# Sheet1.net
KiCad netlist of a schematic drawn in Altium Designer
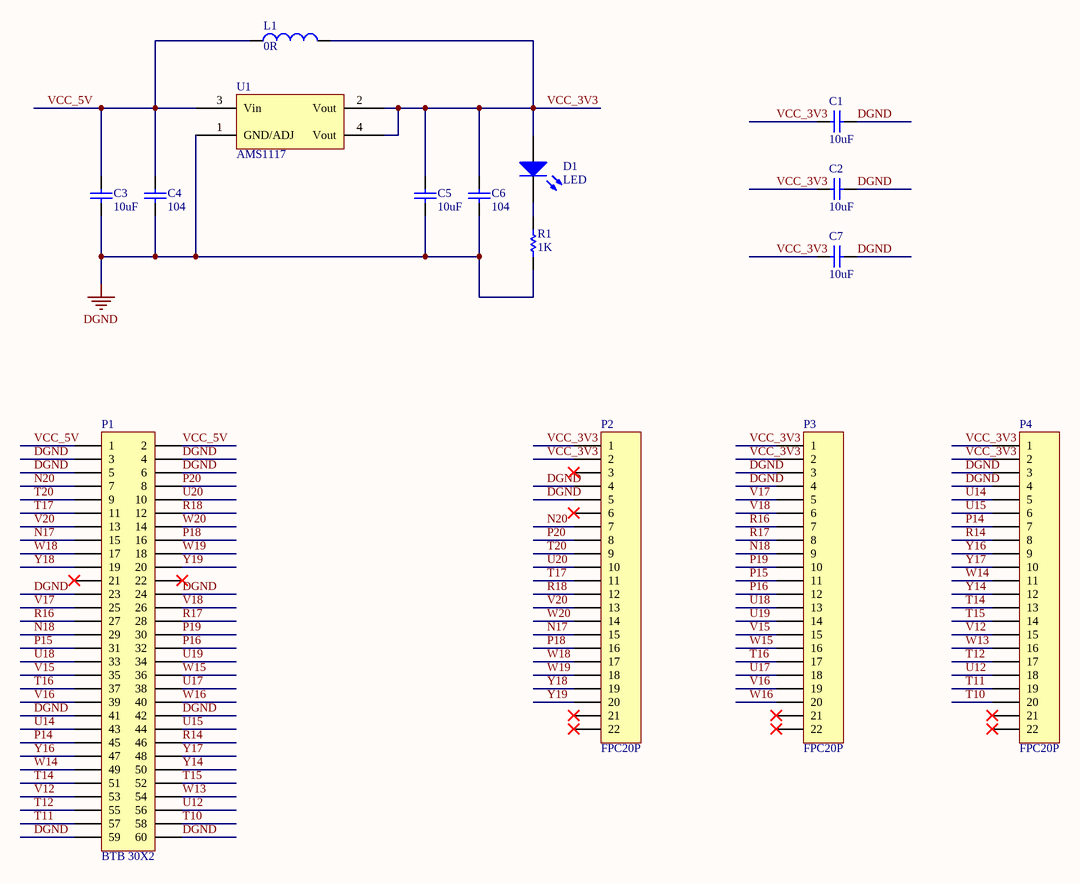
[diagram p0: Sheet1.SchDoc]

(export (version "E")
  (design (tool "Eeschema 10.0.6"))
  (components
    (comp (ref "C1")
      (value "10uF")
      (footprint "R0805")
      (description "Capacitor")
      (fields (field (name "Comment") "Cap") (field (name "PUBLISHER") "Altium Limited"))
      (libsource (lib "Miscellaneous Devices") (part "Cap"))
    )
    (comp (ref "C2")
      (value "10uF")
      (footprint "R0805")
      (description "Capacitor")
      (fields (field (name "Comment") "Cap") (field (name "PUBLISHER") "Altium Limited"))
      (libsource (lib "Miscellaneous Devices") (part "Cap"))
    )
    (comp (ref "C3")
      (value "10uF")
      (footprint "R0805")
      (description "Capacitor")
      (fields (field (name "Comment") "Cap") (field (name "PUBLISHER") "Altium Limited"))
      (libsource (lib "Miscellaneous Devices") (part "Cap"))
    )
    (comp (ref "C4")
      (value "104")
      (footprint "R0805")
      (description "Capacitor")
      (fields (field (name "Comment") "Cap") (field (name "PUBLISHER") "Altium Limited"))
      (libsource (lib "Miscellaneous Devices") (part "Cap"))
    )
    (comp (ref "C5")
      (value "10uF")
      (footprint "R0805")
      (description "Capacitor")
      (fields (field (name "Comment") "Cap") (field (name "PUBLISHER") "Altium Limited"))
      (libsource (lib "Miscellaneous Devices") (part "Cap"))
    )
    (comp (ref "C6")
      (value "104")
      (footprint "R0805")
      (description "Capacitor")
      (fields (field (name "Comment") "Cap") (field (name "PUBLISHER") "Altium Limited"))
      (libsource (lib "Miscellaneous Devices") (part "Cap"))
    )
    (comp (ref "C7")
      (value "10uF")
      (footprint "R0805")
      (description "Capacitor")
      (fields (field (name "Comment") "Cap") (field (name "PUBLISHER") "Altium Limited"))
      (libsource (lib "Miscellaneous Devices") (part "Cap"))
    )
    (comp (ref "D1")
      (value "LED")
      (footprint "LED0805红")
      (description "Typical INFRARED GaAs LED")
      (fields (field (name "PUBLISHER") "Altium Limited"))
      (libsource (lib "Miscellaneous Devices") (part "LED0"))
    )
    (comp (ref "L1")
      (value "0R")
      (footprint "R0805")
      (description "Inductor")
      (fields (field (name "PUBLISHER") "Altium Limited"))
      (libsource (lib "Miscellaneous Devices") (part "Inductor"))
    )
    (comp (ref "P1")
      (value "BTB 30X2")
      (footprint "BTBCON_0.8mm_60P")
      (description "Header, 30-Pin, Dual row")
      (fields (field (name "PUBLISHER") "Altium Limited"))
      (libsource (lib "Miscellaneous Connectors") (part "Header 30X2"))
    )
    (comp (ref "P2")
      (value "FPC20P")
      (footprint "FPC20Pin")
      (description "Header, 22-Pin")
      (fields (field (name "PUBLISHER") "Altium Limited"))
      (libsource (lib "Miscellaneous Connectors") (part "Header 22"))
    )
    (comp (ref "P3")
      (value "FPC20P")
      (footprint "FPC20Pin")
      (description "Header, 22-Pin")
      (fields (field (name "PUBLISHER") "Altium Limited"))
      (libsource (lib "Miscellaneous Connectors") (part "Header 22"))
    )
    (comp (ref "P4")
      (value "FPC20P")
      (footprint "FPC20Pin")
      (description "Header, 22-Pin")
      (fields (field (name "PUBLISHER") "Altium Limited"))
      (libsource (lib "Miscellaneous Connectors") (part "Header 22"))
    )
    (comp (ref "R1")
      (value "1K")
      (footprint "R0805")
      (description "Resistor")
      (fields (field (name "Comment") "Res1") (field (name "PUBLISHER") "Altium Limited"))
      (libsource (lib "Miscellaneous Devices") (part "Res1"))
    )
    (comp (ref "U1")
      (value "AMS1117")
      (footprint "SOT-223   AMS1117")
      (libsource (lib "MySchlib") (part "AMS1117"))
    )
  )
  (nets
    (net (code "1") (name "/N17") (class "Default")
      (node (ref "P1") (pin "15") (pinfunction "15_15") (pintype "passive"))
      (node (ref "P2") (pin "15") (pinfunction "15_15") (pintype "passive"))
    )
    (net (code "2") (name "/N18") (class "Default")
      (node (ref "P1") (pin "29") (pinfunction "29_29") (pintype "passive"))
      (node (ref "P3") (pin "9") (pinfunction "9_9") (pintype "passive"))
    )
    (net (code "3") (name "/N20") (class "Default")
      (node (ref "P1") (pin "7") (pinfunction "7_7") (pintype "passive"))
      (node (ref "P2") (pin "7") (pinfunction "7_7") (pintype "passive"))
    )
    (net (code "4") (name "/P14") (class "Default")
      (node (ref "P1") (pin "45") (pinfunction "45_45") (pintype "passive"))
      (node (ref "P4") (pin "7") (pinfunction "7_7") (pintype "passive"))
    )
    (net (code "5") (name "/P15") (class "Default")
      (node (ref "P1") (pin "31") (pinfunction "31_31") (pintype "passive"))
      (node (ref "P3") (pin "11") (pinfunction "11_11") (pintype "passive"))
    )
    (net (code "6") (name "/P16") (class "Default")
      (node (ref "P1") (pin "32") (pinfunction "32_32") (pintype "passive"))
      (node (ref "P3") (pin "12") (pinfunction "12_12") (pintype "passive"))
    )
    (net (code "7") (name "/P18") (class "Default")
      (node (ref "P1") (pin "16") (pinfunction "16_16") (pintype "passive"))
      (node (ref "P2") (pin "16") (pinfunction "16_16") (pintype "passive"))
    )
    (net (code "8") (name "/P19") (class "Default")
      (node (ref "P1") (pin "30") (pinfunction "30_30") (pintype "passive"))
      (node (ref "P3") (pin "10") (pinfunction "10_10") (pintype "passive"))
    )
    (net (code "9") (name "/P20") (class "Default")
      (node (ref "P1") (pin "8") (pinfunction "8_8") (pintype "passive"))
      (node (ref "P2") (pin "8") (pinfunction "8_8") (pintype "passive"))
    )
    (net (code "10") (name "/R14") (class "Default")
      (node (ref "P1") (pin "46") (pinfunction "46_46") (pintype "passive"))
      (node (ref "P4") (pin "8") (pinfunction "8_8") (pintype "passive"))
    )
    (net (code "11") (name "/R16") (class "Default")
      (node (ref "P1") (pin "27") (pinfunction "27_27") (pintype "passive"))
      (node (ref "P3") (pin "7") (pinfunction "7_7") (pintype "passive"))
    )
    (net (code "12") (name "/R17") (class "Default")
      (node (ref "P1") (pin "28") (pinfunction "28_28") (pintype "passive"))
      (node (ref "P3") (pin "8") (pinfunction "8_8") (pintype "passive"))
    )
    (net (code "13") (name "/R18") (class "Default")
      (node (ref "P1") (pin "12") (pinfunction "12_12") (pintype "passive"))
      (node (ref "P2") (pin "12") (pinfunction "12_12") (pintype "passive"))
    )
    (net (code "14") (name "/T10") (class "Default")
      (node (ref "P1") (pin "58") (pinfunction "58_58") (pintype "passive"))
      (node (ref "P4") (pin "20") (pinfunction "20_20") (pintype "passive"))
    )
    (net (code "15") (name "/T11") (class "Default")
      (node (ref "P1") (pin "57") (pinfunction "57_57") (pintype "passive"))
      (node (ref "P4") (pin "19") (pinfunction "19_19") (pintype "passive"))
    )
    (net (code "16") (name "/T12") (class "Default")
      (node (ref "P1") (pin "55") (pinfunction "55_55") (pintype "passive"))
      (node (ref "P4") (pin "17") (pinfunction "17_17") (pintype "passive"))
    )
    (net (code "17") (name "/T14") (class "Default")
      (node (ref "P1") (pin "51") (pinfunction "51_51") (pintype "passive"))
      (node (ref "P4") (pin "13") (pinfunction "13_13") (pintype "passive"))
    )
    (net (code "18") (name "/T15") (class "Default")
      (node (ref "P1") (pin "52") (pinfunction "52_52") (pintype "passive"))
      (node (ref "P4") (pin "14") (pinfunction "14_14") (pintype "passive"))
    )
    (net (code "19") (name "/T16") (class "Default")
      (node (ref "P1") (pin "37") (pinfunction "37_37") (pintype "passive"))
      (node (ref "P3") (pin "17") (pinfunction "17_17") (pintype "passive"))
    )
    (net (code "20") (name "/T17") (class "Default")
      (node (ref "P1") (pin "11") (pinfunction "11_11") (pintype "passive"))
      (node (ref "P2") (pin "11") (pinfunction "11_11") (pintype "passive"))
    )
    (net (code "21") (name "/T20") (class "Default")
      (node (ref "P1") (pin "9") (pinfunction "9_9") (pintype "passive"))
      (node (ref "P2") (pin "9") (pinfunction "9_9") (pintype "passive"))
    )
    (net (code "22") (name "/U12") (class "Default")
      (node (ref "P1") (pin "56") (pinfunction "56_56") (pintype "passive"))
      (node (ref "P4") (pin "18") (pinfunction "18_18") (pintype "passive"))
    )
    (net (code "23") (name "/U14") (class "Default")
      (node (ref "P1") (pin "43") (pinfunction "43_43") (pintype "passive"))
      (node (ref "P4") (pin "5") (pinfunction "5_5") (pintype "passive"))
    )
    (net (code "24") (name "/U15") (class "Default")
      (node (ref "P1") (pin "44") (pinfunction "44_44") (pintype "passive"))
      (node (ref "P4") (pin "6") (pinfunction "6_6") (pintype "passive"))
    )
    (net (code "25") (name "/U17") (class "Default")
      (node (ref "P1") (pin "38") (pinfunction "38_38") (pintype "passive"))
      (node (ref "P3") (pin "18") (pinfunction "18_18") (pintype "passive"))
    )
    (net (code "26") (name "/U18") (class "Default")
      (node (ref "P1") (pin "33") (pinfunction "33_33") (pintype "passive"))
      (node (ref "P3") (pin "13") (pinfunction "13_13") (pintype "passive"))
    )
    (net (code "27") (name "/U19") (class "Default")
      (node (ref "P1") (pin "34") (pinfunction "34_34") (pintype "passive"))
      (node (ref "P3") (pin "14") (pinfunction "14_14") (pintype "passive"))
    )
    (net (code "28") (name "/U20") (class "Default")
      (node (ref "P1") (pin "10") (pinfunction "10_10") (pintype "passive"))
      (node (ref "P2") (pin "10") (pinfunction "10_10") (pintype "passive"))
    )
    (net (code "29") (name "/V12") (class "Default")
      (node (ref "P1") (pin "53") (pinfunction "53_53") (pintype "passive"))
      (node (ref "P4") (pin "15") (pinfunction "15_15") (pintype "passive"))
    )
    (net (code "30") (name "/V15") (class "Default")
      (node (ref "P1") (pin "35") (pinfunction "35_35") (pintype "passive"))
      (node (ref "P3") (pin "15") (pinfunction "15_15") (pintype "passive"))
    )
    (net (code "31") (name "/V16") (class "Default")
      (node (ref "P1") (pin "39") (pinfunction "39_39") (pintype "passive"))
      (node (ref "P3") (pin "19") (pinfunction "19_19") (pintype "passive"))
    )
    (net (code "32") (name "/V17") (class "Default")
      (node (ref "P1") (pin "25") (pinfunction "25_25") (pintype "passive"))
      (node (ref "P3") (pin "5") (pinfunction "5_5") (pintype "passive"))
    )
    (net (code "33") (name "/V18") (class "Default")
      (node (ref "P1") (pin "26") (pinfunction "26_26") (pintype "passive"))
      (node (ref "P3") (pin "6") (pinfunction "6_6") (pintype "passive"))
    )
    (net (code "34") (name "/V20") (class "Default")
      (node (ref "P1") (pin "13") (pinfunction "13_13") (pintype "passive"))
      (node (ref "P2") (pin "13") (pinfunction "13_13") (pintype "passive"))
    )
    (net (code "35") (name "/VCC_3V3") (class "Default")
      (node (ref "C1") (pin "2") (pinfunction "2_2") (pintype "passive"))
      (node (ref "C2") (pin "2") (pinfunction "2_2") (pintype "passive"))
      (node (ref "C5") (pin "2") (pinfunction "2_2") (pintype "passive"))
      (node (ref "C6") (pin "2") (pinfunction "2_2") (pintype "passive"))
      (node (ref "C7") (pin "2") (pinfunction "2_2") (pintype "passive"))
      (node (ref "D1") (pin "1") (pinfunction "A_1") (pintype "passive"))
      (node (ref "L1") (pin "2") (pinfunction "2_2") (pintype "passive"))
      (node (ref "P2") (pin "1") (pinfunction "1_1") (pintype "passive"))
      (node (ref "P2") (pin "2") (pinfunction "2_2") (pintype "passive"))
      (node (ref "P3") (pin "1") (pinfunction "1_1") (pintype "passive"))
      (node (ref "P3") (pin "2") (pinfunction "2_2") (pintype "passive"))
      (node (ref "P4") (pin "1") (pinfunction "1_1") (pintype "passive"))
      (node (ref "P4") (pin "2") (pinfunction "2_2") (pintype "passive"))
      (node (ref "U1") (pin "2") (pinfunction "Vout_2") (pintype "passive"))
      (node (ref "U1") (pin "4") (pinfunction "Vout_4") (pintype "passive"))
    )
    (net (code "36") (name "/VCC_5V") (class "Default")
      (node (ref "C3") (pin "2") (pinfunction "2_2") (pintype "passive"))
      (node (ref "C4") (pin "2") (pinfunction "2_2") (pintype "passive"))
      (node (ref "L1") (pin "1") (pinfunction "1_1") (pintype "passive"))
      (node (ref "P1") (pin "1") (pinfunction "1_1") (pintype "passive"))
      (node (ref "P1") (pin "2") (pinfunction "2_2") (pintype "passive"))
      (node (ref "U1") (pin "3") (pinfunction "Vin_3") (pintype "passive"))
    )
    (net (code "37") (name "/W13") (class "Default")
      (node (ref "P1") (pin "54") (pinfunction "54_54") (pintype "passive"))
      (node (ref "P4") (pin "16") (pinfunction "16_16") (pintype "passive"))
    )
    (net (code "38") (name "/W14") (class "Default")
      (node (ref "P1") (pin "49") (pinfunction "49_49") (pintype "passive"))
      (node (ref "P4") (pin "11") (pinfunction "11_11") (pintype "passive"))
    )
    (net (code "39") (name "/W15") (class "Default")
      (node (ref "P1") (pin "36") (pinfunction "36_36") (pintype "passive"))
      (node (ref "P3") (pin "16") (pinfunction "16_16") (pintype "passive"))
    )
    (net (code "40") (name "/W16") (class "Default")
      (node (ref "P1") (pin "40") (pinfunction "40_40") (pintype "passive"))
      (node (ref "P3") (pin "20") (pinfunction "20_20") (pintype "passive"))
    )
    (net (code "41") (name "/W18") (class "Default")
      (node (ref "P1") (pin "17") (pinfunction "17_17") (pintype "passive"))
      (node (ref "P2") (pin "17") (pinfunction "17_17") (pintype "passive"))
    )
    (net (code "42") (name "/W19") (class "Default")
      (node (ref "P1") (pin "18") (pinfunction "18_18") (pintype "passive"))
      (node (ref "P2") (pin "18") (pinfunction "18_18") (pintype "passive"))
    )
    (net (code "43") (name "/W20") (class "Default")
      (node (ref "P1") (pin "14") (pinfunction "14_14") (pintype "passive"))
      (node (ref "P2") (pin "14") (pinfunction "14_14") (pintype "passive"))
    )
    (net (code "44") (name "/Y14") (class "Default")
      (node (ref "P1") (pin "50") (pinfunction "50_50") (pintype "passive"))
      (node (ref "P4") (pin "12") (pinfunction "12_12") (pintype "passive"))
    )
    (net (code "45") (name "/Y16") (class "Default")
      (node (ref "P1") (pin "47") (pinfunction "47_47") (pintype "passive"))
      (node (ref "P4") (pin "9") (pinfunction "9_9") (pintype "passive"))
    )
    (net (code "46") (name "/Y17") (class "Default")
      (node (ref "P1") (pin "48") (pinfunction "48_48") (pintype "passive"))
      (node (ref "P4") (pin "10") (pinfunction "10_10") (pintype "passive"))
    )
    (net (code "47") (name "/Y18") (class "Default")
      (node (ref "P1") (pin "19") (pinfunction "19_19") (pintype "passive"))
      (node (ref "P2") (pin "19") (pinfunction "19_19") (pintype "passive"))
    )
    (net (code "48") (name "/Y19") (class "Default")
      (node (ref "P1") (pin "20") (pinfunction "20_20") (pintype "passive"))
      (node (ref "P2") (pin "20") (pinfunction "20_20") (pintype "passive"))
    )
    (net (code "49") (name "DGND") (class "Default")
      (node (ref "C1") (pin "1") (pinfunction "1_1") (pintype "passive"))
      (node (ref "C2") (pin "1") (pinfunction "1_1") (pintype "passive"))
      (node (ref "C3") (pin "1") (pinfunction "1_1") (pintype "passive"))
      (node (ref "C4") (pin "1") (pinfunction "1_1") (pintype "passive"))
      (node (ref "C5") (pin "1") (pinfunction "1_1") (pintype "passive"))
      (node (ref "C6") (pin "1") (pinfunction "1_1") (pintype "passive"))
      (node (ref "C7") (pin "1") (pinfunction "1_1") (pintype "passive"))
      (node (ref "P1") (pin "23") (pinfunction "23_23") (pintype "passive"))
      (node (ref "P1") (pin "24") (pinfunction "24_24") (pintype "passive"))
      (node (ref "P1") (pin "3") (pinfunction "3_3") (pintype "passive"))
      (node (ref "P1") (pin "4") (pinfunction "4_4") (pintype "passive"))
      (node (ref "P1") (pin "41") (pinfunction "41_41") (pintype "passive"))
      (node (ref "P1") (pin "42") (pinfunction "42_42") (pintype "passive"))
      (node (ref "P1") (pin "5") (pinfunction "5_5") (pintype "passive"))
      (node (ref "P1") (pin "59") (pinfunction "59_59") (pintype "passive"))
      (node (ref "P1") (pin "6") (pinfunction "6_6") (pintype "passive"))
      (node (ref "P1") (pin "60") (pinfunction "60_60") (pintype "passive"))
      (node (ref "P2") (pin "4") (pinfunction "4_4") (pintype "passive"))
      (node (ref "P2") (pin "5") (pinfunction "5_5") (pintype "passive"))
      (node (ref "P3") (pin "3") (pinfunction "3_3") (pintype "passive"))
      (node (ref "P3") (pin "4") (pinfunction "4_4") (pintype "passive"))
      (node (ref "P4") (pin "3") (pinfunction "3_3") (pintype "passive"))
      (node (ref "P4") (pin "4") (pinfunction "4_4") (pintype "passive"))
      (node (ref "R1") (pin "1") (pinfunction "1_1") (pintype "passive"))
      (node (ref "U1") (pin "1") (pinfunction "GND/ADJ_1") (pintype "passive"))
    )
    (net (code "50") (name "Net-(D1-K)") (class "Default")
      (node (ref "D1") (pin "2") (pinfunction "K_2") (pintype "passive"))
      (node (ref "R1") (pin "2") (pinfunction "2_2") (pintype "passive"))
    )
    (net (code "51") (name "unconnected-(P1-Pad21)") (class "Default")
      (node (ref "P1") (pin "21") (pinfunction "21_21") (pintype "passive+no_connect"))
    )
    (net (code "52") (name "unconnected-(P1-Pad22)") (class "Default")
      (node (ref "P1") (pin "22") (pinfunction "22_22") (pintype "passive+no_connect"))
    )
    (net (code "53") (name "unconnected-(P2-Pad3)") (class "Default")
      (node (ref "P2") (pin "3") (pinfunction "3_3") (pintype "passive+no_connect"))
    )
    (net (code "54") (name "unconnected-(P2-Pad6)") (class "Default")
      (node (ref "P2") (pin "6") (pinfunction "6_6") (pintype "passive+no_connect"))
    )
    (net (code "55") (name "unconnected-(P2-Pad21)") (class "Default")
      (node (ref "P2") (pin "21") (pinfunction "21_21") (pintype "passive+no_connect"))
    )
    (net (code "56") (name "unconnected-(P2-Pad22)") (class "Default")
      (node (ref "P2") (pin "22") (pinfunction "22_22") (pintype "passive+no_connect"))
    )
    (net (code "57") (name "unconnected-(P3-Pad21)") (class "Default")
      (node (ref "P3") (pin "21") (pinfunction "21_21") (pintype "passive+no_connect"))
    )
    (net (code "58") (name "unconnected-(P3-Pad22)") (class "Default")
      (node (ref "P3") (pin "22") (pinfunction "22_22") (pintype "passive+no_connect"))
    )
    (net (code "59") (name "unconnected-(P4-Pad21)") (class "Default")
      (node (ref "P4") (pin "21") (pinfunction "21_21") (pintype "passive+no_connect"))
    )
    (net (code "60") (name "unconnected-(P4-Pad22)") (class "Default")
      (node (ref "P4") (pin "22") (pinfunction "22_22") (pintype "passive+no_connect"))
    )
  )
)
